# MovimientoC.net
KiCad netlist of a schematic drawn in EAGLE
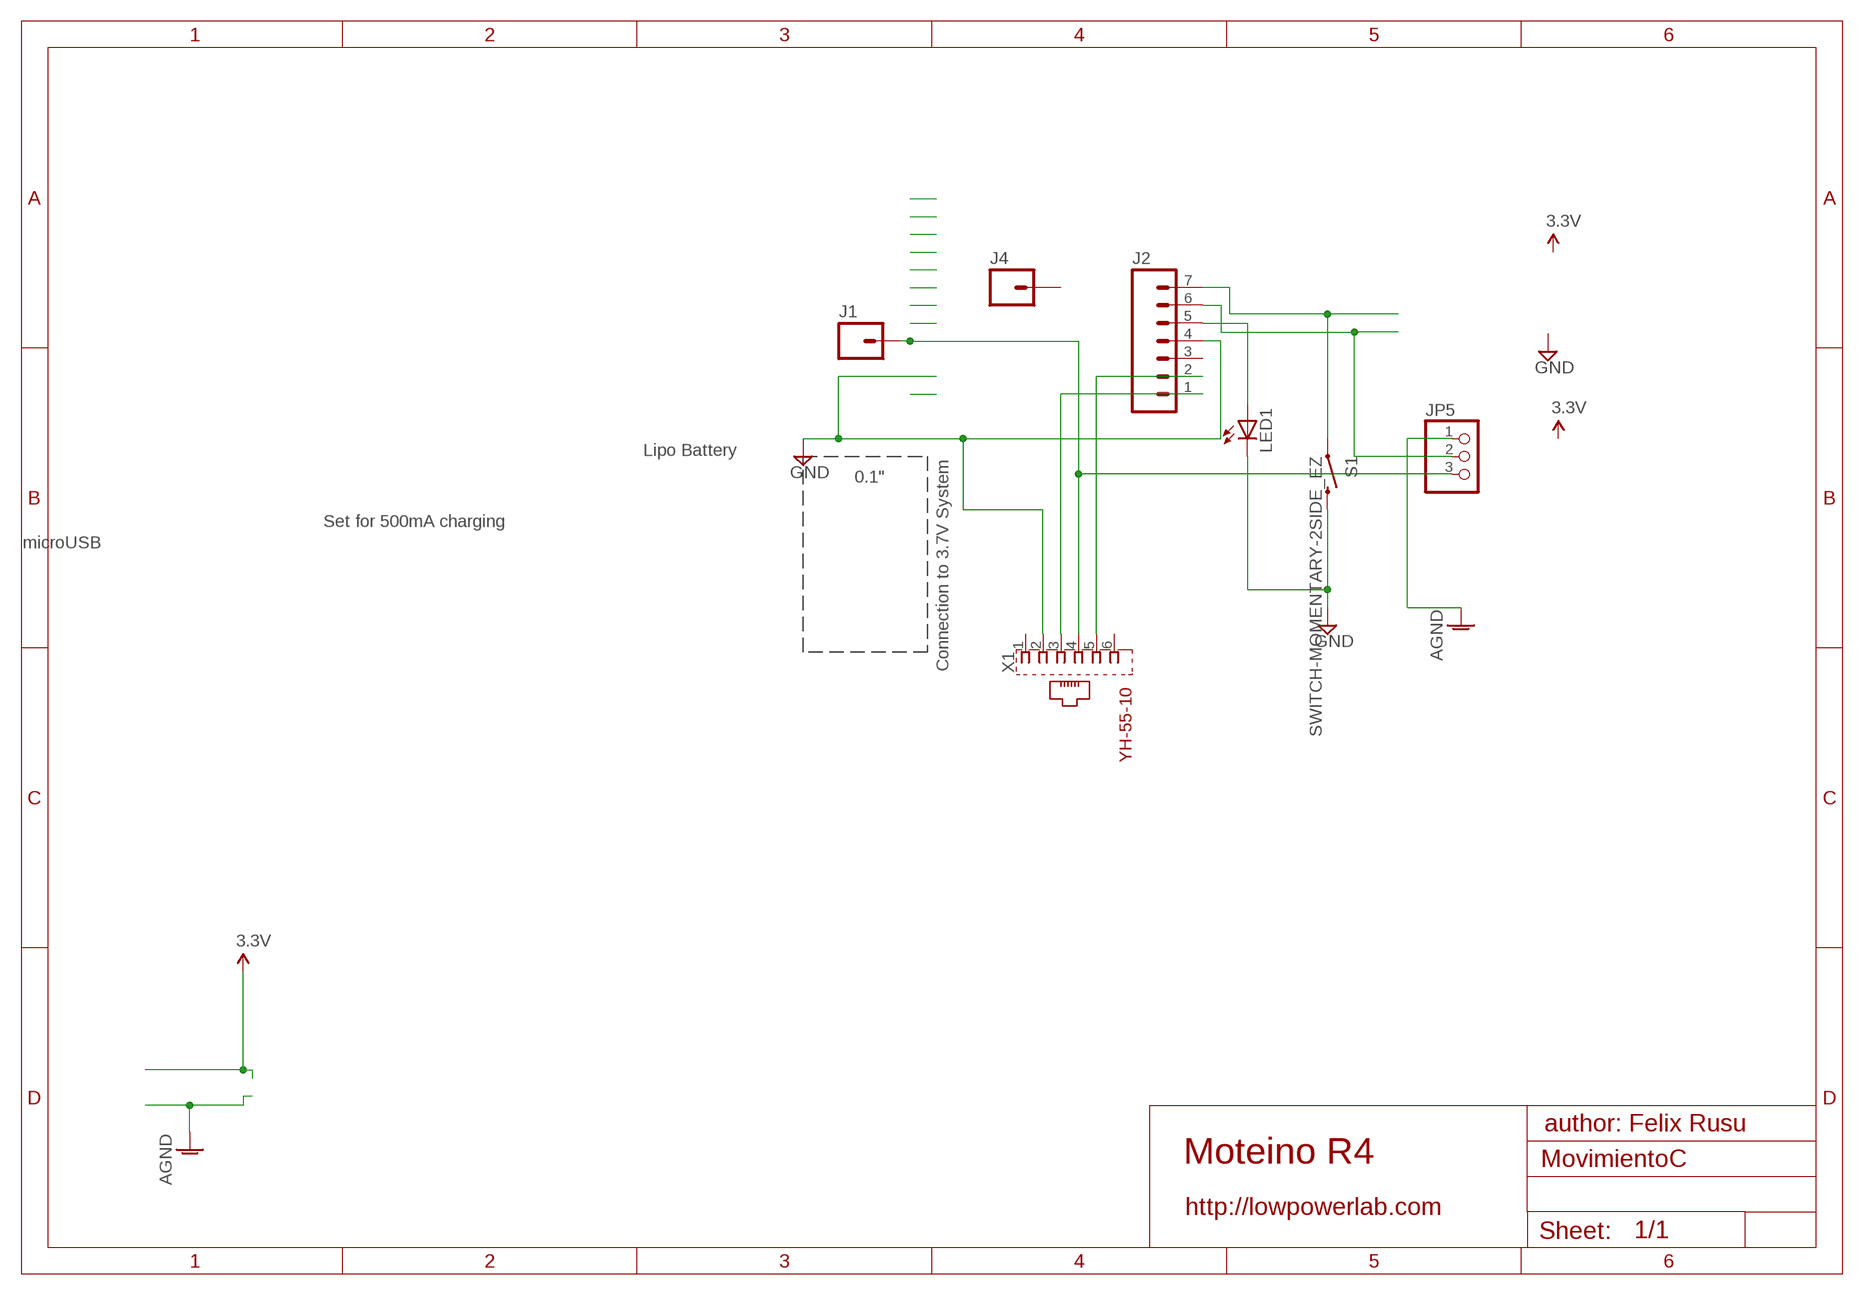
[diagram p0: schematic, sheet 1]

(export (version "E")
  (design (tool "Eeschema 10.0.6"))
  (components
    (comp (ref "J1")
      (value "M01PTH")
      (footprint "eagle-import:1X01")
      (libsource (lib "eagle-import") (part "M01PTH"))
    )
    (comp (ref "J2")
      (value "M07")
      (footprint "eagle-import:1X07")
      (libsource (lib "eagle-import") (part "M07"))
    )
    (comp (ref "J4")
      (value "M01PTH")
      (footprint "eagle-import:1X01")
      (libsource (lib "eagle-import") (part "M01PTH"))
    )
    (comp (ref "JP5")
      (value "PINHD-1X3")
      (footprint "eagle-import:1X03")
      (libsource (lib "eagle-import") (part "PINHD-1X3"))
    )
    (comp (ref "LED1")
      (value "LED3MM")
      (footprint "eagle-import:LED3MM")
      (libsource (lib "eagle-import") (part "LED3MM"))
    )
    (comp (ref "S1")
      (value "SWITCH-MOMENTARY-2SIDE_EZ")
      (footprint "eagle-import:TACTILE-PTH-SIDEEZ")
      (libsource (lib "eagle-import") (part "SWITCH-MOMENTARY-2SIDE_EZ"))
    )
    (comp (ref "X1")
      (value "YH-55-10")
      (footprint "eagle-import:YH-55-10")
      (libsource (lib "eagle-import") (part "YH-55-10"))
    )
  )
  (nets
    (net (code "2") (name "AGND") (class "Default")
      (node (ref "JP5") (pin "1") (pinfunction "1_1") (pintype "passive"))
    )
    (net (code "3") (name "GND") (class "Default")
      (node (ref "J2") (pin "4") (pinfunction "4_4") (pintype "passive"))
      (node (ref "LED1") (pin "K") (pinfunction "C_K") (pintype "passive"))
      (node (ref "S1") (pin "2") (pinfunction "2_2") (pintype "passive"))
      (node (ref "X1") (pin "2") (pinfunction "2_2") (pintype "passive"))
    )
    (net (code "4") (name "Net-(J1-Pad1)") (class "Default")
      (node (ref "J1") (pin "1") (pinfunction "1_1") (pintype "passive"))
      (node (ref "JP5") (pin "3") (pinfunction "3_3") (pintype "passive"))
      (node (ref "X1") (pin "4") (pinfunction "4_4") (pintype "passive"))
    )
    (net (code "5") (name "Net-(J2-Pad1)") (class "Default")
      (node (ref "J2") (pin "1") (pinfunction "1_1") (pintype "passive"))
      (node (ref "X1") (pin "3") (pinfunction "3_3") (pintype "passive"))
    )
    (net (code "6") (name "Net-(J2-Pad2)") (class "Default")
      (node (ref "J2") (pin "2") (pinfunction "2_2") (pintype "passive"))
      (node (ref "X1") (pin "5") (pinfunction "5_5") (pintype "passive"))
    )
    (net (code "7") (name "Net-(J2-Pad5)") (class "Default")
      (node (ref "J2") (pin "5") (pinfunction "5_5") (pintype "passive"))
      (node (ref "LED1") (pin "A") (pinfunction "A_A") (pintype "passive"))
    )
    (net (code "8") (name "Net-(J2-Pad6)") (class "Default")
      (node (ref "J2") (pin "6") (pinfunction "6_6") (pintype "passive"))
      (node (ref "JP5") (pin "2") (pinfunction "2_2") (pintype "passive"))
    )
    (net (code "9") (name "Net-(J2-Pad7)") (class "Default")
      (node (ref "J2") (pin "7") (pinfunction "7_7") (pintype "passive"))
      (node (ref "S1") (pin "1") (pinfunction "1_1") (pintype "passive"))
    )
    (net (code "10") (name "unconnected-(J2-Pad3)") (class "Default")
      (node (ref "J2") (pin "3") (pinfunction "3_3") (pintype "passive"))
    )
    (net (code "11") (name "unconnected-(J4-Pad1)") (class "Default")
      (node (ref "J4") (pin "1") (pinfunction "1_1") (pintype "passive"))
    )
    (net (code "12") (name "unconnected-(X1-Pad1)") (class "Default")
      (node (ref "X1") (pin "1") (pinfunction "1_1") (pintype "passive"))
    )
    (net (code "13") (name "unconnected-(X1-Pad6)") (class "Default")
      (node (ref "X1") (pin "6") (pinfunction "6_6") (pintype "passive"))
    )
  )
)
